# TPS60501.net
KiCad netlist of a schematic drawn in EAGLE
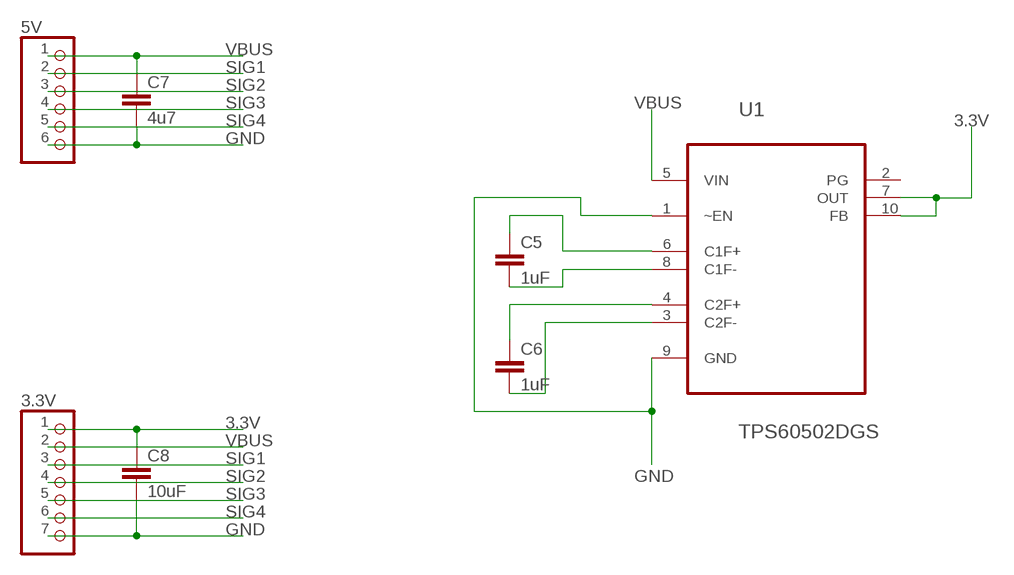
[diagram p0: schematic, sheet 1]

(export (version "E")
  (design (tool "Eeschema 10.0.6"))
  (components
    (comp (ref "3.3V")
      (value "PINHD-1X7")
      (footprint "eagle-import:1X07")
      (libsource (lib "eagle-import") (part "PINHD-1X7"))
    )
    (comp (ref "5V")
      (value "PINHD-1X6")
      (footprint "eagle-import:1X06")
      (libsource (lib "eagle-import") (part "PINHD-1X6"))
    )
    (comp (ref "C5")
      (value "1uF")
      (footprint "eagle-import:C025-050X050")
      (libsource (lib "eagle-import") (part "C-EU025-050X050"))
    )
    (comp (ref "C6")
      (value "1uF")
      (footprint "eagle-import:C025-050X050")
      (libsource (lib "eagle-import") (part "C-EU025-050X050"))
    )
    (comp (ref "C7")
      (value "4u7")
      (footprint "eagle-import:C025-050X050")
      (libsource (lib "eagle-import") (part "C-EU025-050X050"))
    )
    (comp (ref "C8")
      (value "10uF")
      (footprint "eagle-import:C025-050X050")
      (libsource (lib "eagle-import") (part "C-EU025-050X050"))
    )
    (comp (ref "U1")
      (value "TPS60502DGS")
      (footprint "eagle-import:SOP50P490X110-10N")
      (libsource (lib "eagle-import") (part "TPS60502DGS"))
    )
  )
  (nets
    (net (code "1") (name "/3.3V") (class "Default")
      (node (ref "3.3V") (pin "1") (pinfunction "1_1") (pintype "passive"))
      (node (ref "C8") (pin "1") (pinfunction "1_1") (pintype "passive"))
      (node (ref "U1") (pin "10") (pinfunction "FB_10") (pintype "output"))
      (node (ref "U1") (pin "7") (pinfunction "OUT_7") (pintype "output"))
    )
    (net (code "2") (name "/GND") (class "Default")
      (node (ref "3.3V") (pin "7") (pinfunction "7_7") (pintype "passive"))
      (node (ref "5V") (pin "6") (pinfunction "6_6") (pintype "passive"))
      (node (ref "C7") (pin "2") (pinfunction "2_2") (pintype "passive"))
      (node (ref "C8") (pin "2") (pinfunction "2_2") (pintype "passive"))
      (node (ref "U1") (pin "1") (pinfunction "~{EN}_1") (pintype "input"))
      (node (ref "U1") (pin "9") (pinfunction "GND_9") (pintype "passive"))
    )
    (net (code "3") (name "/SIG1") (class "Default")
      (node (ref "3.3V") (pin "3") (pinfunction "3_3") (pintype "passive"))
      (node (ref "5V") (pin "2") (pinfunction "2_2") (pintype "passive"))
    )
    (net (code "4") (name "/SIG2") (class "Default")
      (node (ref "3.3V") (pin "4") (pinfunction "4_4") (pintype "passive"))
      (node (ref "5V") (pin "3") (pinfunction "3_3") (pintype "passive"))
    )
    (net (code "5") (name "/SIG3") (class "Default")
      (node (ref "3.3V") (pin "5") (pinfunction "5_5") (pintype "passive"))
      (node (ref "5V") (pin "4") (pinfunction "4_4") (pintype "passive"))
    )
    (net (code "6") (name "/SIG4") (class "Default")
      (node (ref "3.3V") (pin "6") (pinfunction "6_6") (pintype "passive"))
      (node (ref "5V") (pin "5") (pinfunction "5_5") (pintype "passive"))
    )
    (net (code "7") (name "/VBUS") (class "Default")
      (node (ref "3.3V") (pin "2") (pinfunction "2_2") (pintype "passive"))
      (node (ref "5V") (pin "1") (pinfunction "1_1") (pintype "passive"))
      (node (ref "C7") (pin "1") (pinfunction "1_1") (pintype "passive"))
      (node (ref "U1") (pin "5") (pinfunction "VIN_5") (pintype "power_in"))
    )
    (net (code "8") (name "Net-(U1-C1F+)") (class "Default")
      (node (ref "C5") (pin "1") (pinfunction "1_1") (pintype "passive"))
      (node (ref "U1") (pin "6") (pinfunction "C1F+_6") (pintype "passive"))
    )
    (net (code "9") (name "Net-(U1-C1F-)") (class "Default")
      (node (ref "C5") (pin "2") (pinfunction "2_2") (pintype "passive"))
      (node (ref "U1") (pin "8") (pinfunction "C1F-_8") (pintype "passive"))
    )
    (net (code "10") (name "Net-(U1-C2F+)") (class "Default")
      (node (ref "C6") (pin "1") (pinfunction "1_1") (pintype "passive"))
      (node (ref "U1") (pin "4") (pinfunction "C2F+_4") (pintype "passive"))
    )
    (net (code "11") (name "Net-(U1-C2F-)") (class "Default")
      (node (ref "C6") (pin "2") (pinfunction "2_2") (pintype "passive"))
      (node (ref "U1") (pin "3") (pinfunction "C2F-_3") (pintype "passive"))
    )
    (net (code "12") (name "unconnected-(U1-PG-Pad2)") (class "Default")
      (node (ref "U1") (pin "2") (pinfunction "PG_2") (pintype "output"))
    )
  )
)
